# epiano.net
KiCad netlist of a schematic drawn in EAGLE
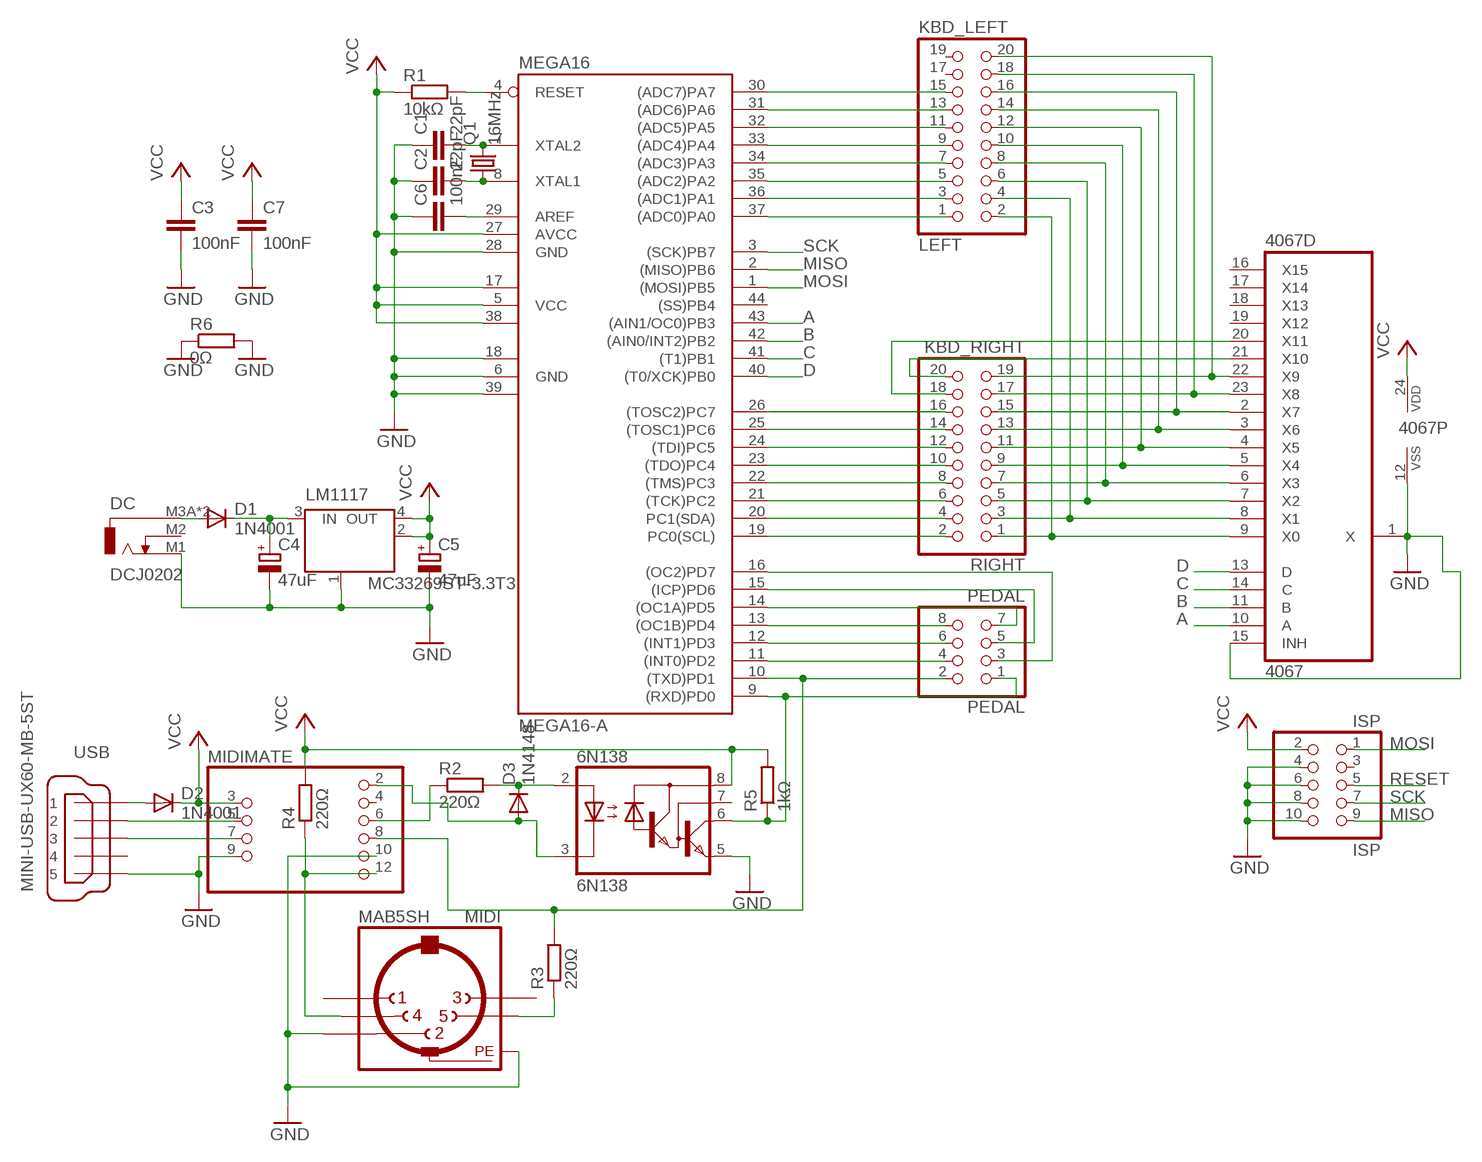
[diagram p0: schematic, sheet 1]

(export (version "E")
  (design (tool "Eeschema 10.0.6"))
  (components
    (comp (ref "6N138")
      (value "6N138")
      (footprint "eagle-import:SMD-8")
      (fields (field (name "MF") "VISHAY/TELEFUNKEN"))
      (libsource (lib "eagle-import") (part "6N138"))
    )
    (comp (ref "4067")
      (value "4067D")
      (footprint "eagle-import:SO24W")
      (libsource (lib "eagle-import") (part "4067D"))
    )
    (comp (ref "C1")
      (value "22pF")
      (footprint "eagle-import:C0805")
      (libsource (lib "eagle-import") (part "C-EUC0805"))
    )
    (comp (ref "C2")
      (value "22pF")
      (footprint "eagle-import:C0805")
      (libsource (lib "eagle-import") (part "C-EUC0805"))
    )
    (comp (ref "C3")
      (value "100nF")
      (footprint "eagle-import:C0805")
      (libsource (lib "eagle-import") (part "C-EUC0805"))
    )
    (comp (ref "C4")
      (value "47uF")
      (footprint "eagle-import:PANASONIC_D")
      (libsource (lib "eagle-import") (part "CPOL-EUD"))
    )
    (comp (ref "C5")
      (value "47uF")
      (footprint "eagle-import:PANASONIC_D")
      (libsource (lib "eagle-import") (part "CPOL-EUD"))
    )
    (comp (ref "C6")
      (value "100nF")
      (footprint "eagle-import:C0805")
      (libsource (lib "eagle-import") (part "C-EUC0805"))
    )
    (comp (ref "C7")
      (value "100nF")
      (footprint "eagle-import:C0805")
      (libsource (lib "eagle-import") (part "C-EUC0805"))
    )
    (comp (ref "D1")
      (value "1N4001")
      (footprint "eagle-import:MELF-MLL41")
      (libsource (lib "eagle-import") (part "DIODE-MELF-MLL41"))
    )
    (comp (ref "D2")
      (value "1N4001")
      (footprint "eagle-import:MELF-MLL41")
      (libsource (lib "eagle-import") (part "DIODE-MELF-MLL41"))
    )
    (comp (ref "D3")
      (value "1N4148")
      (footprint "eagle-import:MINIMELF")
      (libsource (lib "eagle-import") (part "DIODE-MINIMELF"))
    )
    (comp (ref "DC")
      (value "DCJ0202")
      (footprint "eagle-import:DCJ0202")
      (libsource (lib "eagle-import") (part "DCJ0202"))
    )
    (comp (ref "ISP")
      (value "ISP")
      (footprint "eagle-import:2X05SMD")
      (libsource (lib "eagle-import") (part "PINHD-2X5_2.54-SMD"))
    )
    (comp (ref "LEFT")
      (value "KBD_LEFT")
      (footprint "eagle-import:2X10SMD")
      (libsource (lib "eagle-import") (part "PINHD-2X10_2.54-SMD"))
    )
    (comp (ref "LM1117")
      (value "MC33269ST-3.3T3")
      (footprint "eagle-import:SOT223")
      (libsource (lib "eagle-import") (part "MC33269ST-3.3T3"))
    )
    (comp (ref "MEGA16")
      (value "MEGA16-A")
      (footprint "eagle-import:TQFP44")
      (fields (field (name "MPN") "ATMEGA16-16AU"))
      (libsource (lib "eagle-import") (part "MEGA16-A"))
    )
    (comp (ref "MIDI")
      (value "MAB5SH")
      (footprint "eagle-import:MAB5SH")
      (libsource (lib "eagle-import") (part "MAB5SH"))
    )
    (comp (ref "MIDIMATE")
      (value "USBMIDI_2.54-SMD")
      (footprint "eagle-import:USBMIDI")
      (libsource (lib "eagle-import") (part "USBMIDI_2.54-SMD"))
    )
    (comp (ref "PEDAL")
      (value "PEDAL")
      (footprint "eagle-import:2X04SMD")
      (libsource (lib "eagle-import") (part "PINHD-2X4_2.54-SMD"))
    )
    (comp (ref "Q1")
      (value "16MHz")
      (footprint "eagle-import:SM49")
      (libsource (lib "eagle-import") (part "CRYSTALSM49"))
    )
    (comp (ref "R1")
      (value "10kΩ")
      (footprint "eagle-import:R0805")
      (libsource (lib "eagle-import") (part "R-EU_R0805"))
    )
    (comp (ref "R2")
      (value "220Ω")
      (footprint "eagle-import:R0805")
      (libsource (lib "eagle-import") (part "R-EU_R0805"))
    )
    (comp (ref "R3")
      (value "220Ω")
      (footprint "eagle-import:R0805")
      (libsource (lib "eagle-import") (part "R-EU_R0805"))
    )
    (comp (ref "R4")
      (value "220Ω")
      (footprint "eagle-import:R0805")
      (libsource (lib "eagle-import") (part "R-EU_R0805"))
    )
    (comp (ref "R5")
      (value "1kΩ")
      (footprint "eagle-import:R0805")
      (libsource (lib "eagle-import") (part "R-EU_R0805"))
    )
    (comp (ref "R6")
      (value "0Ω")
      (footprint "eagle-import:R1206")
      (libsource (lib "eagle-import") (part "R-EU_R1206"))
    )
    (comp (ref "RIGHT")
      (value "KBD_RIGHT")
      (footprint "eagle-import:2X10SMD")
      (libsource (lib "eagle-import") (part "PINHD-2X10_2.54-SMD"))
    )
    (comp (ref "USB")
      (value "MINI-USB-UX60-MB-5ST")
      (footprint "eagle-import:UX60-MB-5ST")
      (libsource (lib "eagle-import") (part "MINI-USB-UX60-MB-5ST"))
    )
  )
  (nets
    (net (code "1") (name "/A") (class "Default")
      (node (ref "4067") (pin "10") (pinfunction "A_10") (pintype "input"))
      (node (ref "MEGA16") (pin "43") (pinfunction "(AIN1/OC0)PB3_43") (pintype "bidirectional"))
    )
    (net (code "2") (name "/B") (class "Default")
      (node (ref "4067") (pin "11") (pinfunction "B_11") (pintype "input"))
      (node (ref "MEGA16") (pin "42") (pinfunction "(AIN0/INT2)PB2_42") (pintype "bidirectional"))
    )
    (net (code "3") (name "/C") (class "Default")
      (node (ref "4067") (pin "14") (pinfunction "C_14") (pintype "input"))
      (node (ref "MEGA16") (pin "41") (pinfunction "(T1)PB1_41") (pintype "bidirectional"))
    )
    (net (code "4") (name "/D") (class "Default")
      (node (ref "4067") (pin "13") (pinfunction "D_13") (pintype "input"))
      (node (ref "MEGA16") (pin "40") (pinfunction "(T0/XCK)PB0_40") (pintype "bidirectional"))
    )
    (net (code "5") (name "/MISO") (class "Default")
      (node (ref "ISP") (pin "9") (pinfunction "9_9") (pintype "passive"))
      (node (ref "MEGA16") (pin "2") (pinfunction "(MISO)PB6_2") (pintype "bidirectional"))
    )
    (net (code "6") (name "/MOSI") (class "Default")
      (node (ref "ISP") (pin "1") (pinfunction "1_1") (pintype "passive"))
      (node (ref "MEGA16") (pin "1") (pinfunction "(MOSI)PB5_1") (pintype "bidirectional"))
    )
    (net (code "7") (name "/RESET") (class "Default")
      (node (ref "ISP") (pin "5") (pinfunction "5_5") (pintype "passive"))
      (node (ref "MEGA16") (pin "4") (pinfunction "RESET_4") (pintype "input"))
      (node (ref "R1") (pin "2") (pinfunction "2_2") (pintype "passive"))
    )
    (net (code "8") (name "/SCK") (class "Default")
      (node (ref "ISP") (pin "7") (pinfunction "7_7") (pintype "passive"))
      (node (ref "MEGA16") (pin "3") (pinfunction "(SCK)PB7_3") (pintype "bidirectional"))
    )
    (net (code "9") (name "GND") (class "Default")
      (node (ref "4067") (pin "1") (pinfunction "X_1") (pintype "output"))
      (node (ref "4067") (pin "12") (pinfunction "VSS_12") (pintype "power_in"))
      (node (ref "4067") (pin "15") (pinfunction "INH_15") (pintype "input"))
      (node (ref "6N138") (pin "5") (pinfunction "GND_5") (pintype "passive"))
      (node (ref "C1") (pin "1") (pinfunction "1_1") (pintype "passive"))
      (node (ref "C2") (pin "1") (pinfunction "1_1") (pintype "passive"))
      (node (ref "C3") (pin "2") (pinfunction "2_2") (pintype "passive"))
      (node (ref "C4") (pin "-") (pinfunction "-_-") (pintype "passive"))
      (node (ref "C5") (pin "-") (pinfunction "-_-") (pintype "passive"))
      (node (ref "C6") (pin "1") (pinfunction "1_1") (pintype "passive"))
      (node (ref "C7") (pin "2") (pinfunction "2_2") (pintype "passive"))
      (node (ref "DC") (pin "M1") (pinfunction "3_M1") (pintype "passive"))
      (node (ref "ISP") (pin "10") (pinfunction "10_10") (pintype "passive"))
      (node (ref "ISP") (pin "4") (pinfunction "4_4") (pintype "passive"))
      (node (ref "ISP") (pin "6") (pinfunction "6_6") (pintype "passive"))
      (node (ref "ISP") (pin "8") (pinfunction "8_8") (pintype "passive"))
      (node (ref "LM1117") (pin "1") (pinfunction "GND/ADJ_1") (pintype "input"))
      (node (ref "MEGA16") (pin "18") (pinfunction "GND1_18") (pintype "power_in"))
      (node (ref "MEGA16") (pin "28") (pinfunction "GND_28") (pintype "power_in"))
      (node (ref "MEGA16") (pin "39") (pinfunction "GND2_39") (pintype "power_in"))
      (node (ref "MEGA16") (pin "6") (pinfunction "GND_6") (pintype "power_in"))
      (node (ref "MIDI") (pin "2") (pinfunction "2_2") (pintype "passive"))
      (node (ref "MIDI") (pin "PE") (pinfunction "PE_PE") (pintype "power_in"))
      (node (ref "MIDI") (pin "PE@") (pinfunction "PE_PE@") (pintype "power_in"))
      (node (ref "MIDIMATE") (pin "10") (pinfunction "10_10") (pintype "passive"))
      (node (ref "MIDIMATE") (pin "9") (pinfunction "9_9") (pintype "passive"))
      (node (ref "R6") (pin "1") (pinfunction "1_1") (pintype "passive"))
      (node (ref "R6") (pin "2") (pinfunction "2_2") (pintype "passive"))
      (node (ref "USB") (pin "5") (pinfunction "5_5") (pintype "input"))
    )
    (net (code "10") (name "Net-(6N138-A)") (class "Default")
      (node (ref "6N138") (pin "2") (pinfunction "A_2") (pintype "passive"))
      (node (ref "D3") (pin "C") (pinfunction "C_C") (pintype "passive"))
      (node (ref "R2") (pin "2") (pinfunction "2_2") (pintype "passive"))
    )
    (net (code "11") (name "Net-(6N138-C)") (class "Default")
      (node (ref "6N138") (pin "3") (pinfunction "C_3") (pintype "passive"))
      (node (ref "D3") (pin "A") (pinfunction "A_A") (pintype "passive"))
      (node (ref "MIDIMATE") (pin "2") (pinfunction "2_2") (pintype "passive"))
    )
    (net (code "12") (name "Net-(6N138-VO)") (class "Default")
      (node (ref "6N138") (pin "6") (pinfunction "VO_6") (pintype "passive"))
      (node (ref "MEGA16") (pin "9") (pinfunction "(RXD)PD0_9") (pintype "bidirectional"))
      (node (ref "PEDAL") (pin "1") (pinfunction "1_1") (pintype "passive"))
      (node (ref "R5") (pin "1") (pinfunction "1_1") (pintype "passive"))
    )
    (net (code "13") (name "Net-(4067A-X0)") (class "Default")
      (node (ref "4067") (pin "9") (pinfunction "X0_9") (pintype "input"))
      (node (ref "LEFT") (pin "2") (pinfunction "2_2") (pintype "passive"))
      (node (ref "RIGHT") (pin "1") (pinfunction "1_1") (pintype "passive"))
    )
    (net (code "14") (name "Net-(4067A-X1)") (class "Default")
      (node (ref "4067") (pin "8") (pinfunction "X1_8") (pintype "input"))
      (node (ref "LEFT") (pin "4") (pinfunction "4_4") (pintype "passive"))
      (node (ref "RIGHT") (pin "3") (pinfunction "3_3") (pintype "passive"))
    )
    (net (code "15") (name "Net-(4067A-X2)") (class "Default")
      (node (ref "4067") (pin "7") (pinfunction "X2_7") (pintype "input"))
      (node (ref "LEFT") (pin "6") (pinfunction "6_6") (pintype "passive"))
      (node (ref "RIGHT") (pin "5") (pinfunction "5_5") (pintype "passive"))
    )
    (net (code "16") (name "Net-(4067A-X3)") (class "Default")
      (node (ref "4067") (pin "6") (pinfunction "X3_6") (pintype "input"))
      (node (ref "LEFT") (pin "8") (pinfunction "8_8") (pintype "passive"))
      (node (ref "RIGHT") (pin "7") (pinfunction "7_7") (pintype "passive"))
    )
    (net (code "17") (name "Net-(4067A-X4)") (class "Default")
      (node (ref "4067") (pin "5") (pinfunction "X4_5") (pintype "input"))
      (node (ref "LEFT") (pin "10") (pinfunction "10_10") (pintype "passive"))
      (node (ref "RIGHT") (pin "9") (pinfunction "9_9") (pintype "passive"))
    )
    (net (code "18") (name "Net-(4067A-X5)") (class "Default")
      (node (ref "4067") (pin "4") (pinfunction "X5_4") (pintype "input"))
      (node (ref "LEFT") (pin "12") (pinfunction "12_12") (pintype "passive"))
      (node (ref "RIGHT") (pin "11") (pinfunction "11_11") (pintype "passive"))
    )
    (net (code "19") (name "Net-(4067A-X6)") (class "Default")
      (node (ref "4067") (pin "3") (pinfunction "X6_3") (pintype "input"))
      (node (ref "LEFT") (pin "14") (pinfunction "14_14") (pintype "passive"))
      (node (ref "RIGHT") (pin "13") (pinfunction "13_13") (pintype "passive"))
    )
    (net (code "20") (name "Net-(4067A-X7)") (class "Default")
      (node (ref "4067") (pin "2") (pinfunction "X7_2") (pintype "input"))
      (node (ref "LEFT") (pin "16") (pinfunction "16_16") (pintype "passive"))
      (node (ref "RIGHT") (pin "15") (pinfunction "15_15") (pintype "passive"))
    )
    (net (code "21") (name "Net-(4067A-X8)") (class "Default")
      (node (ref "4067") (pin "23") (pinfunction "X8_23") (pintype "input"))
      (node (ref "LEFT") (pin "18") (pinfunction "18_18") (pintype "passive"))
      (node (ref "RIGHT") (pin "17") (pinfunction "17_17") (pintype "passive"))
    )
    (net (code "22") (name "Net-(4067A-X9)") (class "Default")
      (node (ref "4067") (pin "22") (pinfunction "X9_22") (pintype "input"))
      (node (ref "LEFT") (pin "20") (pinfunction "20_20") (pintype "passive"))
      (node (ref "RIGHT") (pin "19") (pinfunction "19_19") (pintype "passive"))
    )
    (net (code "23") (name "Net-(4067A-X10)") (class "Default")
      (node (ref "4067") (pin "21") (pinfunction "X10_21") (pintype "input"))
      (node (ref "RIGHT") (pin "20") (pinfunction "20_20") (pintype "passive"))
    )
    (net (code "24") (name "Net-(4067A-X11)") (class "Default")
      (node (ref "4067") (pin "20") (pinfunction "X11_20") (pintype "input"))
      (node (ref "RIGHT") (pin "18") (pinfunction "18_18") (pintype "passive"))
    )
    (net (code "25") (name "Net-(D1-PadA)") (class "Default")
      (node (ref "D1") (pin "A") (pinfunction "A_A") (pintype "passive"))
      (node (ref "DC") (pin "M3A") (pinfunction "1_M3A") (pintype "passive"))
      (node (ref "DC") (pin "M3B") (pinfunction "1_M3B") (pintype "passive"))
    )
    (net (code "26") (name "Net-(D2-PadA)") (class "Default")
      (node (ref "D2") (pin "A") (pinfunction "A_A") (pintype "passive"))
      (node (ref "USB") (pin "1") (pinfunction "1_1") (pintype "input"))
    )
    (net (code "27") (name "Net-(LM1117-IN)") (class "Default")
      (node (ref "C4") (pin "+") (pinfunction "+_+") (pintype "passive"))
      (node (ref "D1") (pin "C") (pinfunction "C_C") (pintype "passive"))
      (node (ref "LM1117") (pin "3") (pinfunction "IN_3") (pintype "input"))
    )
    (net (code "28") (name "Net-(MEGA16-(ADC0)PA0)") (class "Default")
      (node (ref "LEFT") (pin "1") (pinfunction "1_1") (pintype "passive"))
      (node (ref "MEGA16") (pin "37") (pinfunction "(ADC0)PA0_37") (pintype "bidirectional"))
    )
    (net (code "29") (name "Net-(MEGA16-(ADC1)PA1)") (class "Default")
      (node (ref "LEFT") (pin "3") (pinfunction "3_3") (pintype "passive"))
      (node (ref "MEGA16") (pin "36") (pinfunction "(ADC1)PA1_36") (pintype "bidirectional"))
    )
    (net (code "30") (name "Net-(MEGA16-(ADC2)PA2)") (class "Default")
      (node (ref "LEFT") (pin "5") (pinfunction "5_5") (pintype "passive"))
      (node (ref "MEGA16") (pin "35") (pinfunction "(ADC2)PA2_35") (pintype "bidirectional"))
    )
    (net (code "31") (name "Net-(MEGA16-(ADC3)PA3)") (class "Default")
      (node (ref "LEFT") (pin "7") (pinfunction "7_7") (pintype "passive"))
      (node (ref "MEGA16") (pin "34") (pinfunction "(ADC3)PA3_34") (pintype "bidirectional"))
    )
    (net (code "32") (name "Net-(MEGA16-(ADC4)PA4)") (class "Default")
      (node (ref "LEFT") (pin "9") (pinfunction "9_9") (pintype "passive"))
      (node (ref "MEGA16") (pin "33") (pinfunction "(ADC4)PA4_33") (pintype "bidirectional"))
    )
    (net (code "33") (name "Net-(MEGA16-(ADC5)PA5)") (class "Default")
      (node (ref "LEFT") (pin "11") (pinfunction "11_11") (pintype "passive"))
      (node (ref "MEGA16") (pin "32") (pinfunction "(ADC5)PA5_32") (pintype "bidirectional"))
    )
    (net (code "34") (name "Net-(MEGA16-(ADC6)PA6)") (class "Default")
      (node (ref "LEFT") (pin "13") (pinfunction "13_13") (pintype "passive"))
      (node (ref "MEGA16") (pin "31") (pinfunction "(ADC6)PA6_31") (pintype "bidirectional"))
    )
    (net (code "35") (name "Net-(MEGA16-(ADC7)PA7)") (class "Default")
      (node (ref "LEFT") (pin "15") (pinfunction "15_15") (pintype "passive"))
      (node (ref "MEGA16") (pin "30") (pinfunction "(ADC7)PA7_30") (pintype "bidirectional"))
    )
    (net (code "36") (name "Net-(MEGA16-(ICP)PD6)") (class "Default")
      (node (ref "MEGA16") (pin "15") (pinfunction "(ICP)PD6_15") (pintype "bidirectional"))
      (node (ref "PEDAL") (pin "5") (pinfunction "5_5") (pintype "passive"))
    )
    (net (code "37") (name "Net-(MEGA16-(INT0)PD2)") (class "Default")
      (node (ref "MEGA16") (pin "11") (pinfunction "(INT0)PD2_11") (pintype "bidirectional"))
      (node (ref "PEDAL") (pin "4") (pinfunction "4_4") (pintype "passive"))
    )
    (net (code "38") (name "Net-(MEGA16-(INT1)PD3)") (class "Default")
      (node (ref "MEGA16") (pin "12") (pinfunction "(INT1)PD3_12") (pintype "bidirectional"))
      (node (ref "PEDAL") (pin "6") (pinfunction "6_6") (pintype "passive"))
    )
    (net (code "39") (name "Net-(MEGA16-(OC1A)PD5)") (class "Default")
      (node (ref "MEGA16") (pin "14") (pinfunction "(OC1A)PD5_14") (pintype "bidirectional"))
      (node (ref "PEDAL") (pin "7") (pinfunction "7_7") (pintype "passive"))
    )
    (net (code "40") (name "Net-(MEGA16-(OC1B)PD4)") (class "Default")
      (node (ref "MEGA16") (pin "13") (pinfunction "(OC1B)PD4_13") (pintype "bidirectional"))
      (node (ref "PEDAL") (pin "8") (pinfunction "8_8") (pintype "passive"))
    )
    (net (code "41") (name "Net-(MEGA16-(OC2)PD7)") (class "Default")
      (node (ref "MEGA16") (pin "16") (pinfunction "(OC2)PD7_16") (pintype "bidirectional"))
      (node (ref "PEDAL") (pin "3") (pinfunction "3_3") (pintype "passive"))
    )
    (net (code "42") (name "Net-(MEGA16-(TCK)PC2)") (class "Default")
      (node (ref "MEGA16") (pin "21") (pinfunction "(TCK)PC2_21") (pintype "bidirectional"))
      (node (ref "RIGHT") (pin "6") (pinfunction "6_6") (pintype "passive"))
    )
    (net (code "43") (name "Net-(MEGA16-(TDI)PC5)") (class "Default")
      (node (ref "MEGA16") (pin "24") (pinfunction "(TDI)PC5_24") (pintype "bidirectional"))
      (node (ref "RIGHT") (pin "12") (pinfunction "12_12") (pintype "passive"))
    )
    (net (code "44") (name "Net-(MEGA16-(TDO)PC4)") (class "Default")
      (node (ref "MEGA16") (pin "23") (pinfunction "(TDO)PC4_23") (pintype "bidirectional"))
      (node (ref "RIGHT") (pin "10") (pinfunction "10_10") (pintype "passive"))
    )
    (net (code "45") (name "Net-(MEGA16-(TMS)PC3)") (class "Default")
      (node (ref "MEGA16") (pin "22") (pinfunction "(TMS)PC3_22") (pintype "bidirectional"))
      (node (ref "RIGHT") (pin "8") (pinfunction "8_8") (pintype "passive"))
    )
    (net (code "46") (name "Net-(MEGA16-(TOSC1)PC6)") (class "Default")
      (node (ref "MEGA16") (pin "25") (pinfunction "(TOSC1)PC6_25") (pintype "bidirectional"))
      (node (ref "RIGHT") (pin "14") (pinfunction "14_14") (pintype "passive"))
    )
    (net (code "47") (name "Net-(MEGA16-(TOSC2)PC7)") (class "Default")
      (node (ref "MEGA16") (pin "26") (pinfunction "(TOSC2)PC7_26") (pintype "bidirectional"))
      (node (ref "RIGHT") (pin "16") (pinfunction "16_16") (pintype "passive"))
    )
    (net (code "48") (name "Net-(MEGA16-(TXD)PD1)") (class "Default")
      (node (ref "MEGA16") (pin "10") (pinfunction "(TXD)PD1_10") (pintype "bidirectional"))
      (node (ref "MIDIMATE") (pin "8") (pinfunction "8_8") (pintype "passive"))
      (node (ref "PEDAL") (pin "2") (pinfunction "2_2") (pintype "passive"))
      (node (ref "R3") (pin "2") (pinfunction "2_2") (pintype "passive"))
    )
    (net (code "49") (name "Net-(MEGA16-AREF)") (class "Default")
      (node (ref "C6") (pin "2") (pinfunction "2_2") (pintype "passive"))
      (node (ref "MEGA16") (pin "29") (pinfunction "AREF_29") (pintype "passive"))
    )
    (net (code "50") (name "Net-(MEGA16-PC0(SCL))") (class "Default")
      (node (ref "MEGA16") (pin "19") (pinfunction "PC0(SCL)_19") (pintype "bidirectional"))
      (node (ref "RIGHT") (pin "2") (pinfunction "2_2") (pintype "passive"))
    )
    (net (code "51") (name "Net-(MEGA16-PC1(SDA))") (class "Default")
      (node (ref "MEGA16") (pin "20") (pinfunction "PC1(SDA)_20") (pintype "bidirectional"))
      (node (ref "RIGHT") (pin "4") (pinfunction "4_4") (pintype "passive"))
    )
    (net (code "52") (name "Net-(MEGA16-XTAL1)") (class "Default")
      (node (ref "C2") (pin "2") (pinfunction "2_2") (pintype "passive"))
      (node (ref "MEGA16") (pin "8") (pinfunction "XTAL1_8") (pintype "bidirectional"))
      (node (ref "Q1") (pin "1") (pinfunction "1_1") (pintype "passive"))
    )
    (net (code "53") (name "Net-(MEGA16-XTAL2)") (class "Default")
      (node (ref "C1") (pin "2") (pinfunction "2_2") (pintype "passive"))
      (node (ref "MEGA16") (pin "7") (pinfunction "XTAL2_7") (pintype "bidirectional"))
      (node (ref "Q1") (pin "2") (pinfunction "2_2") (pintype "passive"))
    )
    (net (code "54") (name "Net-(MIDI-Pad4)") (class "Default")
      (node (ref "MIDI") (pin "4") (pinfunction "4_4") (pintype "passive"))
      (node (ref "MIDIMATE") (pin "12") (pinfunction "12_12") (pintype "passive"))
      (node (ref "R4") (pin "1") (pinfunction "1_1") (pintype "passive"))
    )
    (net (code "55") (name "Net-(MIDI-Pad5)") (class "Default")
      (node (ref "MIDI") (pin "5") (pinfunction "5_5") (pintype "passive"))
      (node (ref "R3") (pin "1") (pinfunction "1_1") (pintype "passive"))
    )
    (net (code "56") (name "Net-(MIDIMATE-Pad5)") (class "Default")
      (node (ref "MIDIMATE") (pin "5") (pinfunction "5_5") (pintype "passive"))
      (node (ref "USB") (pin "2") (pinfunction "2_2") (pintype "input"))
    )
    (net (code "57") (name "Net-(MIDIMATE-Pad6)") (class "Default")
      (node (ref "MIDIMATE") (pin "6") (pinfunction "6_6") (pintype "passive"))
      (node (ref "R2") (pin "1") (pinfunction "1_1") (pintype "passive"))
    )
    (net (code "58") (name "Net-(MIDIMATE-Pad7)") (class "Default")
      (node (ref "MIDIMATE") (pin "7") (pinfunction "7_7") (pintype "passive"))
      (node (ref "USB") (pin "3") (pinfunction "3_3") (pintype "input"))
    )
    (net (code "59") (name "VCC") (class "Default")
      (node (ref "4067") (pin "24") (pinfunction "VDD_24") (pintype "power_in"))
      (node (ref "6N138") (pin "8") (pinfunction "VCC_8") (pintype "passive"))
      (node (ref "C3") (pin "1") (pinfunction "1_1") (pintype "passive"))
      (node (ref "C5") (pin "+") (pinfunction "+_+") (pintype "passive"))
      (node (ref "C7") (pin "1") (pinfunction "1_1") (pintype "passive"))
      (node (ref "D2") (pin "C") (pinfunction "C_C") (pintype "passive"))
      (node (ref "ISP") (pin "2") (pinfunction "2_2") (pintype "passive"))
      (node (ref "LM1117") (pin "2") (pinfunction "OUT_2") (pintype "passive"))
      (node (ref "LM1117") (pin "4") (pinfunction "OUT_4") (pintype "passive"))
      (node (ref "MEGA16") (pin "17") (pinfunction "VCC1_17") (pintype "power_in"))
      (node (ref "MEGA16") (pin "27") (pinfunction "AVCC_27") (pintype "power_in"))
      (node (ref "MEGA16") (pin "38") (pinfunction "VCC2_38") (pintype "power_in"))
      (node (ref "MEGA16") (pin "5") (pinfunction "VCC_5") (pintype "power_in"))
      (node (ref "MIDIMATE") (pin "3") (pinfunction "3_3") (pintype "passive"))
      (node (ref "R1") (pin "1") (pinfunction "1_1") (pintype "passive"))
      (node (ref "R4") (pin "2") (pinfunction "2_2") (pintype "passive"))
      (node (ref "R5") (pin "2") (pinfunction "2_2") (pintype "passive"))
    )
    (net (code "60") (name "unconnected-(6N138-VB-Pad7)") (class "Default")
      (node (ref "6N138") (pin "7") (pinfunction "VB_7") (pintype "passive"))
    )
    (net (code "61") (name "unconnected-(4067A-X12-Pad19)") (class "Default")
      (node (ref "4067") (pin "19") (pinfunction "X12_19") (pintype "input"))
    )
    (net (code "62") (name "unconnected-(4067A-X13-Pad18)") (class "Default")
      (node (ref "4067") (pin "18") (pinfunction "X13_18") (pintype "input"))
    )
    (net (code "63") (name "unconnected-(4067A-X14-Pad17)") (class "Default")
      (node (ref "4067") (pin "17") (pinfunction "X14_17") (pintype "input"))
    )
    (net (code "64") (name "unconnected-(4067A-X15-Pad16)") (class "Default")
      (node (ref "4067") (pin "16") (pinfunction "X15_16") (pintype "input"))
    )
    (net (code "65") (name "unconnected-(DC-2-PadM2)") (class "Default")
      (node (ref "DC") (pin "M2") (pinfunction "2_M2") (pintype "passive"))
    )
    (net (code "66") (name "unconnected-(ISP-Pad3)") (class "Default")
      (node (ref "ISP") (pin "3") (pinfunction "3_3") (pintype "passive"))
    )
    (net (code "67") (name "unconnected-(LEFT-Pad17)") (class "Default")
      (node (ref "LEFT") (pin "17") (pinfunction "17_17") (pintype "passive"))
    )
    (net (code "68") (name "unconnected-(LEFT-Pad19)") (class "Default")
      (node (ref "LEFT") (pin "19") (pinfunction "19_19") (pintype "passive"))
    )
    (net (code "69") (name "unconnected-(MEGA16-(SS)PB4-Pad44)") (class "Default")
      (node (ref "MEGA16") (pin "44") (pinfunction "(SS)PB4_44") (pintype "bidirectional"))
    )
    (net (code "70") (name "unconnected-(MIDI-Pad1)") (class "Default")
      (node (ref "MIDI") (pin "1") (pinfunction "1_1") (pintype "passive"))
    )
    (net (code "71") (name "unconnected-(MIDI-Pad3)") (class "Default")
      (node (ref "MIDI") (pin "3") (pinfunction "3_3") (pintype "passive"))
    )
    (net (code "72") (name "unconnected-(MIDIMATE-Pad4)") (class "Default")
      (node (ref "MIDIMATE") (pin "4") (pinfunction "4_4") (pintype "passive"))
    )
    (net (code "73") (name "unconnected-(USB-Pad4)") (class "Default")
      (node (ref "USB") (pin "4") (pinfunction "4_4") (pintype "input"))
    )
  )
)
